# SC10033E1_3.net
KiCad netlist of a schematic drawn in Altium Designer
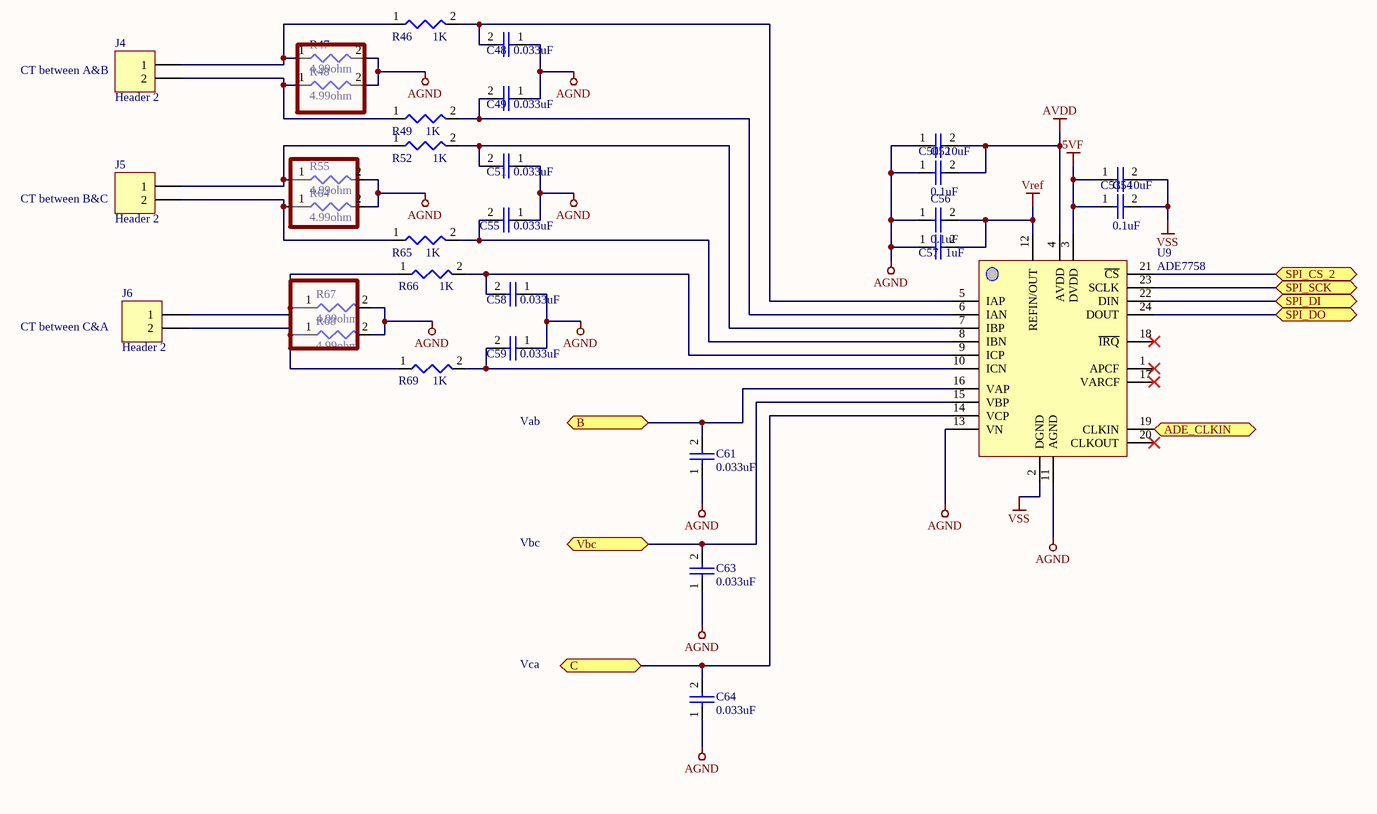
[diagram p0: SC10033E1_3.SchDoc]

(export (version "E")
  (design (tool "Eeschema 10.0.6"))
  (components
    (comp (ref "C48")
      (value "0.033uF")
      (footprint "C0805")
      (description "CAP SMD X7R 50V 10% 0.033uF 0805 ROHS")
      (fields (field (name "MANUFACTURER") "Murata") (field (name "Comment") "CAP"))
      (libsource (lib "enlogic") (part "CAP"))
    )
    (comp (ref "C49")
      (value "0.033uF")
      (footprint "C0805")
      (description "CAP SMD X7R 50V 10% 0.033uF 0805 ROHS")
      (fields (field (name "MANUFACTURER") "Murata") (field (name "Comment") "CAP"))
      (libsource (lib "enlogic") (part "CAP"))
    )
    (comp (ref "C50")
      (value "10uF")
      (footprint "C0805")
      (description "CAP SMD CR X5R 16V 10% 10uF 0805 ROHS")
      (fields (field (name "MANUFACTURER") "Murata"))
      (libsource (lib "enlogic") (part "CAP"))
    )
    (comp (ref "C51")
      (value "0.033uF")
      (footprint "C0805")
      (description "CAP SMD X7R 50V 10% 0.033uF 0805 ROHS")
      (fields (field (name "MANUFACTURER") "Murata") (field (name "Comment") "CAP"))
      (libsource (lib "enlogic") (part "CAP"))
    )
    (comp (ref "C52")
      (value "0.1uF")
      (footprint "C0805")
      (description "CAP SMD CR X7R 50V 10% 0.1uF 0805 ROHS")
      (fields (field (name "MANUFACTURER") "YAGEO") (field (name "Comment") "CAP"))
      (libsource (lib "enlogic") (part "CAP"))
    )
    (comp (ref "C53")
      (value "10uF")
      (footprint "C0805")
      (description "CAP SMD CR X5R 16V 10% 10uF 0805 ROHS")
      (fields (field (name "MANUFACTURER") "Murata"))
      (libsource (lib "enlogic") (part "CAP"))
    )
    (comp (ref "C54")
      (value "0.1uF")
      (footprint "C0805")
      (description "CAP SMD CR X7R 50V 10% 0.1uF 0805 ROHS")
      (fields (field (name "MANUFACTURER") "YAGEO") (field (name "Comment") "CAP"))
      (libsource (lib "enlogic") (part "CAP"))
    )
    (comp (ref "C55")
      (value "0.033uF")
      (footprint "C0805")
      (description "CAP SMD X7R 50V 10% 0.033uF 0805 ROHS")
      (fields (field (name "MANUFACTURER") "Murata") (field (name "Comment") "CAP"))
      (libsource (lib "enlogic") (part "CAP"))
    )
    (comp (ref "C56")
      (value "0.1uF")
      (footprint "C0805")
      (description "CAP SMD CR X7R 50V 10% 0.1uF 0805 ROHS")
      (fields (field (name "MANUFACTURER") "YAGEO") (field (name "Comment") "CAP"))
      (libsource (lib "enlogic") (part "CAP"))
    )
    (comp (ref "C57")
      (value "1uF")
      (footprint "C0805")
      (description "CAP SMD CR X7R 50V 10% 1uF 0805 ROHS")
      (fields (field (name "MANUFACTURER") "YAGEO") (field (name "Comment") "CAP"))
      (libsource (lib "enlogic") (part "CAP"))
    )
    (comp (ref "C58")
      (value "0.033uF")
      (footprint "C0805")
      (description "CAP SMD X7R 50V 10% 0.033uF 0805 ROHS")
      (fields (field (name "MANUFACTURER") "Murata") (field (name "Comment") "CAP"))
      (libsource (lib "enlogic") (part "CAP"))
    )
    (comp (ref "C59")
      (value "0.033uF")
      (footprint "C0805")
      (description "CAP SMD X7R 50V 10% 0.033uF 0805 ROHS")
      (fields (field (name "MANUFACTURER") "Murata") (field (name "Comment") "CAP"))
      (libsource (lib "enlogic") (part "CAP"))
    )
    (comp (ref "C61")
      (value "0.033uF")
      (footprint "C0805")
      (description "CAP SMD X7R 50V 10% 0.033uF 0805 ROHS")
      (fields (field (name "MANUFACTURER") "Murata") (field (name "Comment") "CAP"))
      (libsource (lib "enlogic") (part "CAP"))
    )
    (comp (ref "C63")
      (value "0.033uF")
      (footprint "C0805")
      (description "CAP SMD X7R 50V 10% 0.033uF 0805 ROHS")
      (fields (field (name "MANUFACTURER") "Murata") (field (name "Comment") "CAP"))
      (libsource (lib "enlogic") (part "CAP"))
    )
    (comp (ref "C64")
      (value "0.033uF")
      (footprint "C0805")
      (description "CAP SMD X7R 50V 10% 0.033uF 0805 ROHS")
      (fields (field (name "MANUFACTURER") "Murata") (field (name "Comment") "CAP"))
      (libsource (lib "enlogic") (part "CAP"))
    )
    (comp (ref "J4")
      (value "Header 2")
      (footprint "533980271_sd")
      (description "CONNECTOR 1.25mm Pitch Header, Surface Mount, Vertical, Lead-Free, 2 Circuits")
      (fields (field (name "MANUFACTURER") "MOLEX"))
      (libsource (lib "enlogic") (part "Header 2"))
    )
    (comp (ref "J5")
      (value "Header 2")
      (footprint "533980271_sd")
      (description "CONNECTOR 1.25mm Pitch Header, Surface Mount, Vertical, Lead-Free, 2 Circuits")
      (fields (field (name "MANUFACTURER") "MOLEX"))
      (libsource (lib "enlogic") (part "Header 2"))
    )
    (comp (ref "J6")
      (value "Header 2")
      (footprint "533980271_sd")
      (description "CONNECTOR 1.25mm Pitch Header, Surface Mount, Vertical, Lead-Free, 2 Circuits")
      (fields (field (name "MANUFACTURER") "MOLEX"))
      (libsource (lib "enlogic") (part "Header 2"))
    )
    (comp (ref "R46")
      (value "1K")
      (footprint "R0805")
      (description "RES THICK_FILM SMD 1K 1% 1/8W ROHS 0805")
      (fields (field (name "MANUFACTURER") "YAGEO") (field (name "Comment") "RES"))
      (libsource (lib "enlogic") (part "RES"))
    )
    (comp (ref "R47")
      (value "4.99ohm")
      (footprint "R0805")
      (description "RES THIN_FILM SMD 4.99 ohm 0.1% 1/8W ±25ppm/℃ ROHS 0805")
      (fields (field (name "MANUFACTURER") "YAGEO") (field (name "Comment") "RES"))
      (libsource (lib "enlogic") (part "RES"))
    )
    (comp (ref "R48")
      (value "4.99ohm")
      (footprint "R0805")
      (description "RES THIN_FILM SMD 4.99 ohm 0.1% 1/8W ±25ppm/℃ ROHS 0805")
      (fields (field (name "MANUFACTURER") "YAGEO") (field (name "Comment") "RES"))
      (libsource (lib "enlogic") (part "RES"))
    )
    (comp (ref "R49")
      (value "1K")
      (footprint "R0805")
      (description "RES THICK_FILM SMD 1K 1% 1/8W ROHS 0805")
      (fields (field (name "MANUFACTURER") "YAGEO") (field (name "Comment") "RES"))
      (libsource (lib "enlogic") (part "RES"))
    )
    (comp (ref "R52")
      (value "1K")
      (footprint "R0805")
      (description "RES THICK_FILM SMD 1K 1% 1/8W ROHS 0805")
      (fields (field (name "MANUFACTURER") "YAGEO") (field (name "Comment") "RES"))
      (libsource (lib "enlogic") (part "RES"))
    )
    (comp (ref "R55")
      (value "4.99ohm")
      (footprint "R0805")
      (description "RES THIN_FILM SMD 4.99 ohm 0.1% 1/8W ±25ppm/℃ ROHS 0805")
      (fields (field (name "MANUFACTURER") "YAGEO") (field (name "Comment") "RES"))
      (libsource (lib "enlogic") (part "RES"))
    )
    (comp (ref "R64")
      (value "4.99ohm")
      (footprint "R0805")
      (description "RES THIN_FILM SMD 4.99 ohm 0.1% 1/8W ±25ppm/℃ ROHS 0805")
      (fields (field (name "MANUFACTURER") "YAGEO") (field (name "Comment") "RES"))
      (libsource (lib "enlogic") (part "RES"))
    )
    (comp (ref "R65")
      (value "1K")
      (footprint "R0805")
      (description "RES THICK_FILM SMD 1K 1% 1/8W ROHS 0805")
      (fields (field (name "MANUFACTURER") "YAGEO") (field (name "Comment") "RES"))
      (libsource (lib "enlogic") (part "RES"))
    )
    (comp (ref "R66")
      (value "1K")
      (footprint "R0805")
      (description "RES THICK_FILM SMD 1K 1% 1/8W ROHS 0805")
      (fields (field (name "MANUFACTURER") "YAGEO") (field (name "Comment") "RES"))
      (libsource (lib "enlogic") (part "RES"))
    )
    (comp (ref "R67")
      (value "4.99ohm")
      (footprint "R0805")
      (description "RES THIN_FILM SMD 4.99 ohm 0.1% 1/8W ±25ppm/℃ ROHS 0805")
      (fields (field (name "MANUFACTURER") "YAGEO") (field (name "Comment") "RES"))
      (libsource (lib "enlogic") (part "RES"))
    )
    (comp (ref "R68")
      (value "4.99ohm")
      (footprint "R0805")
      (description "RES THIN_FILM SMD 4.99 ohm 0.1% 1/8W ±25ppm/℃ ROHS 0805")
      (fields (field (name "MANUFACTURER") "YAGEO") (field (name "Comment") "RES"))
      (libsource (lib "enlogic") (part "RES"))
    )
    (comp (ref "R69")
      (value "1K")
      (footprint "R0805")
      (description "RES THICK_FILM SMD 1K 1% 1/8W ROHS 0805")
      (fields (field (name "MANUFACTURER") "YAGEO") (field (name "Comment") "RES"))
      (libsource (lib "enlogic") (part "RES"))
    )
    (comp (ref "U9")
      (value "ADE7758")
      (footprint "SOIC24-W")
      (description "IC Energy Measurement,Irms,VA,VAR,Vrms,Watt,Output:Pulsed&SPI,SOIC_W-24,ROHS")
      (fields (field (name "MANUFACTURER") "ANALOG DEVICES"))
      (libsource (lib "enlogic") (part "ADE7758"))
    )
  )
  (nets
    (net (code "1") (name "/ADE_CLKIN") (class "Default")
      (node (ref "U9") (pin "19") (pinfunction "CLKIN_19") (pintype "passive"))
    )
    (net (code "2") (name "/B") (class "Default")
      (node (ref "C61") (pin "2") (pinfunction "2_2") (pintype "passive"))
      (node (ref "U9") (pin "16") (pinfunction "VAP_16") (pintype "passive"))
    )
    (net (code "3") (name "/C") (class "Default")
      (node (ref "C64") (pin "2") (pinfunction "2_2") (pintype "passive"))
      (node (ref "U9") (pin "14") (pinfunction "VCP_14") (pintype "passive"))
    )
    (net (code "4") (name "/SPI_CS_2") (class "Default")
      (node (ref "U9") (pin "21") (pinfunction "~{CS}_21") (pintype "passive"))
    )
    (net (code "5") (name "/SPI_DI") (class "Default")
      (node (ref "U9") (pin "22") (pinfunction "DIN_22") (pintype "passive"))
    )
    (net (code "6") (name "/SPI_DO") (class "Default")
      (node (ref "U9") (pin "24") (pinfunction "DOUT_24") (pintype "passive"))
    )
    (net (code "7") (name "/SPI_SCK") (class "Default")
      (node (ref "U9") (pin "23") (pinfunction "SCLK_23") (pintype "passive"))
    )
    (net (code "8") (name "/Vbc") (class "Default")
      (node (ref "C63") (pin "2") (pinfunction "2_2") (pintype "passive"))
      (node (ref "U9") (pin "15") (pinfunction "VBP_15") (pintype "passive"))
    )
    (net (code "9") (name "5VF") (class "Default")
      (node (ref "C53") (pin "1") (pinfunction "1_1") (pintype "passive"))
      (node (ref "C54") (pin "1") (pinfunction "1_1") (pintype "passive"))
      (node (ref "U9") (pin "3") (pinfunction "DVDD_3") (pintype "passive"))
    )
    (net (code "10") (name "AGND") (class "Default")
      (node (ref "C48") (pin "1") (pinfunction "1_1") (pintype "passive"))
      (node (ref "C49") (pin "1") (pinfunction "1_1") (pintype "passive"))
      (node (ref "C50") (pin "1") (pinfunction "1_1") (pintype "passive"))
      (node (ref "C51") (pin "1") (pinfunction "1_1") (pintype "passive"))
      (node (ref "C52") (pin "1") (pinfunction "1_1") (pintype "passive"))
      (node (ref "C55") (pin "1") (pinfunction "1_1") (pintype "passive"))
      (node (ref "C56") (pin "1") (pinfunction "1_1") (pintype "passive"))
      (node (ref "C57") (pin "1") (pinfunction "1_1") (pintype "passive"))
      (node (ref "C58") (pin "1") (pinfunction "1_1") (pintype "passive"))
      (node (ref "C59") (pin "1") (pinfunction "1_1") (pintype "passive"))
      (node (ref "C61") (pin "1") (pinfunction "1_1") (pintype "passive"))
      (node (ref "C63") (pin "1") (pinfunction "1_1") (pintype "passive"))
      (node (ref "C64") (pin "1") (pinfunction "1_1") (pintype "passive"))
      (node (ref "R47") (pin "2") (pinfunction "2_2") (pintype "passive"))
      (node (ref "R48") (pin "2") (pinfunction "2_2") (pintype "passive"))
      (node (ref "R55") (pin "2") (pinfunction "2_2") (pintype "passive"))
      (node (ref "R64") (pin "2") (pinfunction "2_2") (pintype "passive"))
      (node (ref "R67") (pin "2") (pinfunction "2_2") (pintype "passive"))
      (node (ref "R68") (pin "2") (pinfunction "2_2") (pintype "passive"))
      (node (ref "U9") (pin "11") (pinfunction "AGND_11") (pintype "passive"))
      (node (ref "U9") (pin "13") (pinfunction "VN_13") (pintype "passive"))
    )
    (net (code "11") (name "AVDD") (class "Default")
      (node (ref "C50") (pin "2") (pinfunction "2_2") (pintype "passive"))
      (node (ref "C52") (pin "2") (pinfunction "2_2") (pintype "passive"))
      (node (ref "U9") (pin "4") (pinfunction "AVDD_4") (pintype "passive"))
    )
    (net (code "12") (name "Net-(J4-Pad1)") (class "Default")
      (node (ref "J4") (pin "1") (pinfunction "1_1") (pintype "passive"))
      (node (ref "R46") (pin "1") (pinfunction "1_1") (pintype "passive"))
      (node (ref "R47") (pin "1") (pinfunction "1_1") (pintype "passive"))
    )
    (net (code "13") (name "Net-(J4-Pad2)") (class "Default")
      (node (ref "J4") (pin "2") (pinfunction "2_2") (pintype "passive"))
      (node (ref "R48") (pin "1") (pinfunction "1_1") (pintype "passive"))
      (node (ref "R49") (pin "1") (pinfunction "1_1") (pintype "passive"))
    )
    (net (code "14") (name "Net-(J5-Pad1)") (class "Default")
      (node (ref "J5") (pin "1") (pinfunction "1_1") (pintype "passive"))
      (node (ref "R52") (pin "1") (pinfunction "1_1") (pintype "passive"))
      (node (ref "R55") (pin "1") (pinfunction "1_1") (pintype "passive"))
    )
    (net (code "15") (name "Net-(J5-Pad2)") (class "Default")
      (node (ref "J5") (pin "2") (pinfunction "2_2") (pintype "passive"))
      (node (ref "R64") (pin "1") (pinfunction "1_1") (pintype "passive"))
      (node (ref "R65") (pin "1") (pinfunction "1_1") (pintype "passive"))
    )
    (net (code "16") (name "Net-(J6-Pad1)") (class "Default")
      (node (ref "J6") (pin "1") (pinfunction "1_1") (pintype "passive"))
      (node (ref "R66") (pin "1") (pinfunction "1_1") (pintype "passive"))
      (node (ref "R67") (pin "1") (pinfunction "1_1") (pintype "passive"))
    )
    (net (code "17") (name "Net-(J6-Pad2)") (class "Default")
      (node (ref "J6") (pin "2") (pinfunction "2_2") (pintype "passive"))
      (node (ref "R68") (pin "1") (pinfunction "1_1") (pintype "passive"))
      (node (ref "R69") (pin "1") (pinfunction "1_1") (pintype "passive"))
    )
    (net (code "18") (name "Net-(U9-IAN)") (class "Default")
      (node (ref "C49") (pin "2") (pinfunction "2_2") (pintype "passive"))
      (node (ref "R49") (pin "2") (pinfunction "2_2") (pintype "passive"))
      (node (ref "U9") (pin "6") (pinfunction "IAN_6") (pintype "passive"))
    )
    (net (code "19") (name "Net-(U9-IAP)") (class "Default")
      (node (ref "C48") (pin "2") (pinfunction "2_2") (pintype "passive"))
      (node (ref "R46") (pin "2") (pinfunction "2_2") (pintype "passive"))
      (node (ref "U9") (pin "5") (pinfunction "IAP_5") (pintype "passive"))
    )
    (net (code "20") (name "Net-(U9-IBN)") (class "Default")
      (node (ref "C55") (pin "2") (pinfunction "2_2") (pintype "passive"))
      (node (ref "R65") (pin "2") (pinfunction "2_2") (pintype "passive"))
      (node (ref "U9") (pin "8") (pinfunction "IBN_8") (pintype "passive"))
    )
    (net (code "21") (name "Net-(U9-IBP)") (class "Default")
      (node (ref "C51") (pin "2") (pinfunction "2_2") (pintype "passive"))
      (node (ref "R52") (pin "2") (pinfunction "2_2") (pintype "passive"))
      (node (ref "U9") (pin "7") (pinfunction "IBP_7") (pintype "passive"))
    )
    (net (code "22") (name "Net-(U9-ICN)") (class "Default")
      (node (ref "C59") (pin "2") (pinfunction "2_2") (pintype "passive"))
      (node (ref "R69") (pin "2") (pinfunction "2_2") (pintype "passive"))
      (node (ref "U9") (pin "10") (pinfunction "ICN_10") (pintype "passive"))
    )
    (net (code "23") (name "Net-(U9-ICP)") (class "Default")
      (node (ref "C58") (pin "2") (pinfunction "2_2") (pintype "passive"))
      (node (ref "R66") (pin "2") (pinfunction "2_2") (pintype "passive"))
      (node (ref "U9") (pin "9") (pinfunction "ICP_9") (pintype "passive"))
    )
    (net (code "24") (name "VSS") (class "Default")
      (node (ref "C53") (pin "2") (pinfunction "2_2") (pintype "passive"))
      (node (ref "C54") (pin "2") (pinfunction "2_2") (pintype "passive"))
      (node (ref "U9") (pin "2") (pinfunction "DGND_2") (pintype "passive"))
    )
    (net (code "25") (name "Vref") (class "Default")
      (node (ref "C56") (pin "2") (pinfunction "2_2") (pintype "passive"))
      (node (ref "C57") (pin "2") (pinfunction "2_2") (pintype "passive"))
      (node (ref "U9") (pin "12") (pinfunction "REFIN/OUT_12") (pintype "passive"))
    )
    (net (code "26") (name "unconnected-(U9-APCF-Pad1)") (class "Default")
      (node (ref "U9") (pin "1") (pinfunction "APCF_1") (pintype "passive+no_connect"))
    )
    (net (code "27") (name "unconnected-(U9-CLKOUT-Pad20)") (class "Default")
      (node (ref "U9") (pin "20") (pinfunction "CLKOUT_20") (pintype "passive+no_connect"))
    )
    (net (code "28") (name "unconnected-(U9-VARCF-Pad17)") (class "Default")
      (node (ref "U9") (pin "17") (pinfunction "VARCF_17") (pintype "passive+no_connect"))
    )
    (net (code "29") (name "unconnected-(U9-~{IRQ}-Pad18)") (class "Default")
      (node (ref "U9") (pin "18") (pinfunction "~{IRQ}_18") (pintype "passive+no_connect"))
    )
  )
)
